# Lightcontrol.net
KiCad netlist of a schematic drawn in EAGLE
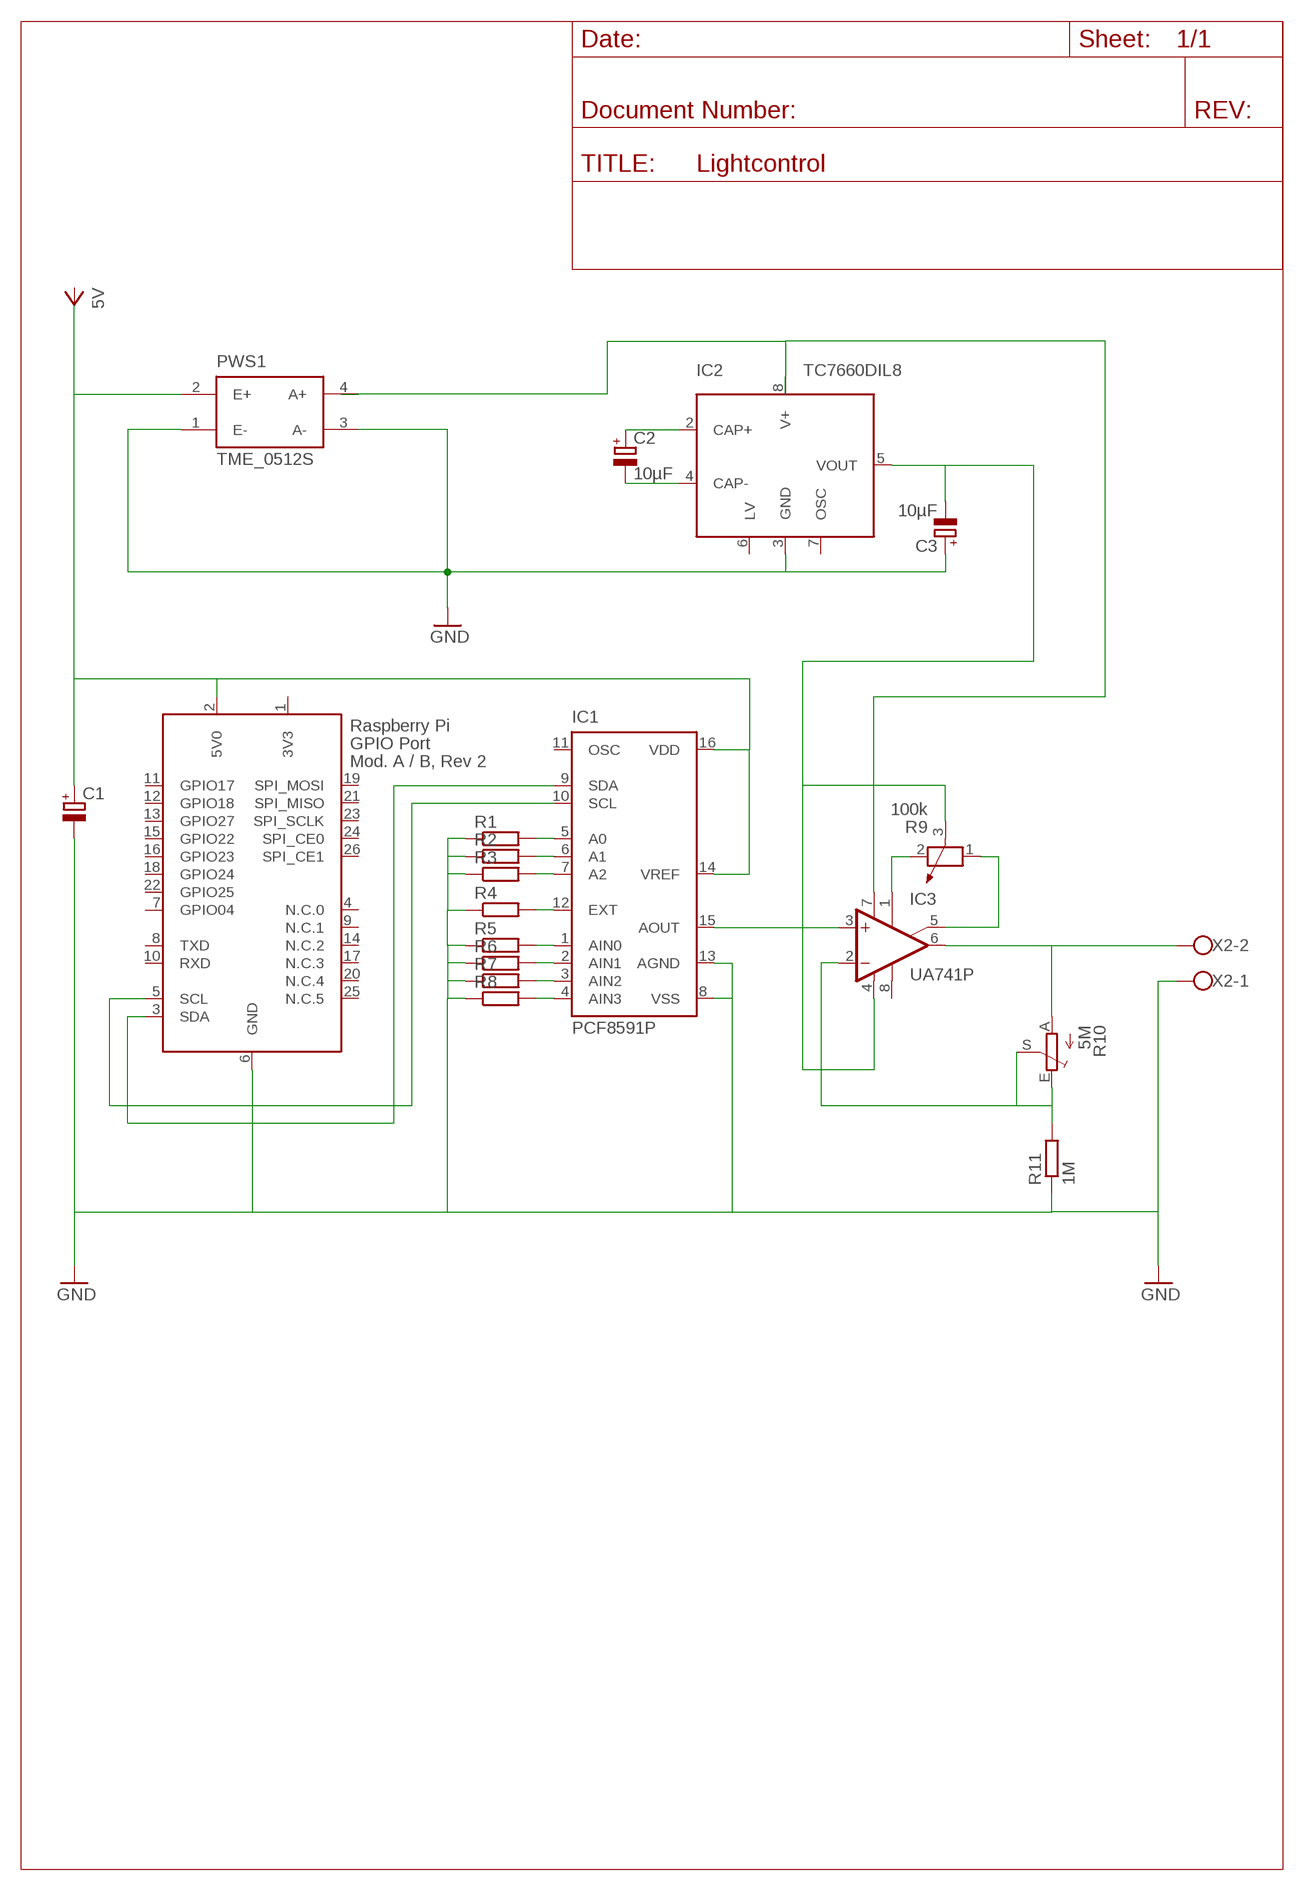
[diagram p0: schematic, sheet 1]

(export (version "E")
  (design (tool "Eeschema 10.0.6"))
  (components
    (comp (ref "C1")
      (value "CPOL-EUE1.8-4")
      (footprint "eagle-import:E1,8-4")
      (libsource (lib "eagle-import") (part "CPOL-EUE1.8-4"))
    )
    (comp (ref "C2")
      (value "10µF")
      (footprint "eagle-import:E1,8-4")
      (libsource (lib "eagle-import") (part "CPOL-EUE1.8-4"))
    )
    (comp (ref "C3")
      (value "10µF")
      (footprint "eagle-import:E1,8-4")
      (libsource (lib "eagle-import") (part "CPOL-EUE1.8-4"))
    )
    (comp (ref "IC1")
      (value "PCF8591P")
      (footprint "eagle-import:DIL16")
      (fields (field (name "MF") "FARNELL"))
      (libsource (lib "eagle-import") (part "PCF8591P"))
    )
    (comp (ref "IC2")
      (value "TC7660DIL8")
      (footprint "eagle-import:DIL8")
      (libsource (lib "eagle-import") (part "TC7660DIL8"))
    )
    (comp (ref "IC3")
      (value "UA741P")
      (footprint "eagle-import:DIL08")
      (libsource (lib "eagle-import") (part "741PUA"))
    )
    (comp (ref "PWS1")
      (value "TME_0512S")
      (footprint "eagle-import:TMEXXXXS")
      (fields (field (name "MPN") "TME 0512S"))
      (libsource (lib "eagle-import") (part "TME_S0512"))
    )
    (comp (ref "R1")
      (value "R-EU_0204/5")
      (footprint "eagle-import:0204_5")
      (libsource (lib "eagle-import") (part "R-EU_0204/5"))
    )
    (comp (ref "R2")
      (value "R-EU_0204/5")
      (footprint "eagle-import:0204_5")
      (libsource (lib "eagle-import") (part "R-EU_0204/5"))
    )
    (comp (ref "R3")
      (value "R-EU_0204/5")
      (footprint "eagle-import:0204_5")
      (libsource (lib "eagle-import") (part "R-EU_0204/5"))
    )
    (comp (ref "R4")
      (value "R-EU_0204/5")
      (footprint "eagle-import:0204_5")
      (libsource (lib "eagle-import") (part "R-EU_0204/5"))
    )
    (comp (ref "R5")
      (value "R-EU_0204/5")
      (footprint "eagle-import:0204_5")
      (libsource (lib "eagle-import") (part "R-EU_0204/5"))
    )
    (comp (ref "R6")
      (value "R-EU_0204/5")
      (footprint "eagle-import:0204_5")
      (libsource (lib "eagle-import") (part "R-EU_0204/5"))
    )
    (comp (ref "R7")
      (value "R-EU_0204/5")
      (footprint "eagle-import:0204_5")
      (libsource (lib "eagle-import") (part "R-EU_0204/5"))
    )
    (comp (ref "R8")
      (value "R-EU_0204/5")
      (footprint "eagle-import:0204_5")
      (libsource (lib "eagle-import") (part "R-EU_0204/5"))
    )
    (comp (ref "R9")
      (value "100k")
      (footprint "eagle-import:PT-10S")
      (libsource (lib "eagle-import") (part "POTENTIOMETER_PT-10S"))
    )
    (comp (ref "R10")
      (value "5M")
      (footprint "eagle-import:ST15")
      (libsource (lib "eagle-import") (part "TRIM_EU-ST15"))
    )
    (comp (ref "R11")
      (value "1M")
      (footprint "eagle-import:0204_5")
      (libsource (lib "eagle-import") (part "R-EU_0204/5"))
    )
    (comp (ref "X1")
      (value "RASPI_GPIO_AB_PIN")
      (footprint "eagle-import:RASPI_GPIO_AB_PIN")
      (libsource (lib "eagle-import") (part "RASPI_GPIO_AB_PIN"))
    )
    (comp (ref "X2")
      (value "W237-102")
      (footprint "eagle-import:W237-102")
      (fields (field (name "MPN") "237-102"))
      (libsource (lib "eagle-import") (part "W237-102"))
    )
  )
  (nets
    (net (code "1") (name "/3V3") (class "Default")
      (node (ref "X1") (pin "1") (pinfunction "3V3_1") (pintype "power_in"))
    )
    (net (code "3") (name "GND") (class "Default")
      (node (ref "C1") (pin "-") (pinfunction "-_-") (pintype "passive"))
      (node (ref "C3") (pin "+") (pinfunction "+_+") (pintype "passive"))
      (node (ref "IC1") (pin "13") (pinfunction "AGND_13") (pintype "power_in"))
      (node (ref "IC1") (pin "8") (pinfunction "VSS_8") (pintype "power_in"))
      (node (ref "IC2") (pin "3") (pinfunction "GND_3") (pintype "bidirectional"))
      (node (ref "PWS1") (pin "1") (pinfunction "E-_1") (pintype "input"))
      (node (ref "PWS1") (pin "3") (pinfunction "A-_3") (pintype "output"))
      (node (ref "R1") (pin "1") (pinfunction "1_1") (pintype "passive"))
      (node (ref "R11") (pin "1") (pinfunction "1_1") (pintype "passive"))
      (node (ref "R2") (pin "1") (pinfunction "1_1") (pintype "passive"))
      (node (ref "R3") (pin "1") (pinfunction "1_1") (pintype "passive"))
      (node (ref "R4") (pin "1") (pinfunction "1_1") (pintype "passive"))
      (node (ref "R5") (pin "1") (pinfunction "1_1") (pintype "passive"))
      (node (ref "R6") (pin "1") (pinfunction "1_1") (pintype "passive"))
      (node (ref "R7") (pin "1") (pinfunction "1_1") (pintype "passive"))
      (node (ref "R8") (pin "1") (pinfunction "1_1") (pintype "passive"))
      (node (ref "X1") (pin "6") (pinfunction "GND_6") (pintype "power_in"))
      (node (ref "X2") (pin "1") (pinfunction "KL_1") (pintype "passive"))
    )
    (net (code "4") (name "Net-(IC1-A0)") (class "Default")
      (node (ref "IC1") (pin "5") (pinfunction "A0_5") (pintype "input"))
      (node (ref "R1") (pin "2") (pinfunction "2_2") (pintype "passive"))
    )
    (net (code "5") (name "Net-(IC1-A1)") (class "Default")
      (node (ref "IC1") (pin "6") (pinfunction "A1_6") (pintype "input"))
      (node (ref "R2") (pin "2") (pinfunction "2_2") (pintype "passive"))
    )
    (net (code "6") (name "Net-(IC1-A2)") (class "Default")
      (node (ref "IC1") (pin "7") (pinfunction "A2_7") (pintype "input"))
      (node (ref "R3") (pin "2") (pinfunction "2_2") (pintype "passive"))
    )
    (net (code "7") (name "Net-(IC1-AIN0)") (class "Default")
      (node (ref "IC1") (pin "1") (pinfunction "AIN0_1") (pintype "input"))
      (node (ref "R5") (pin "2") (pinfunction "2_2") (pintype "passive"))
    )
    (net (code "8") (name "Net-(IC1-AIN1)") (class "Default")
      (node (ref "IC1") (pin "2") (pinfunction "AIN1_2") (pintype "input"))
      (node (ref "R6") (pin "2") (pinfunction "2_2") (pintype "passive"))
    )
    (net (code "9") (name "Net-(IC1-AIN2)") (class "Default")
      (node (ref "IC1") (pin "3") (pinfunction "AIN2_3") (pintype "input"))
      (node (ref "R7") (pin "2") (pinfunction "2_2") (pintype "passive"))
    )
    (net (code "10") (name "Net-(IC1-AIN3)") (class "Default")
      (node (ref "IC1") (pin "4") (pinfunction "AIN3_4") (pintype "input"))
      (node (ref "R8") (pin "2") (pinfunction "2_2") (pintype "passive"))
    )
    (net (code "11") (name "Net-(IC1-AOUT)") (class "Default")
      (node (ref "IC1") (pin "15") (pinfunction "AOUT_15") (pintype "output"))
      (node (ref "IC3") (pin "3") (pinfunction "+IN_3") (pintype "input"))
    )
    (net (code "12") (name "Net-(IC1-EXT)") (class "Default")
      (node (ref "IC1") (pin "12") (pinfunction "EXT_12") (pintype "input"))
      (node (ref "R4") (pin "2") (pinfunction "2_2") (pintype "passive"))
    )
    (net (code "13") (name "Net-(IC1-SCL)") (class "Default")
      (node (ref "IC1") (pin "10") (pinfunction "SCL_10") (pintype "input"))
      (node (ref "X1") (pin "5") (pinfunction "SCL_5") (pintype "bidirectional"))
    )
    (net (code "14") (name "Net-(IC1-SDA)") (class "Default")
      (node (ref "IC1") (pin "9") (pinfunction "SDA_9") (pintype "bidirectional"))
      (node (ref "X1") (pin "3") (pinfunction "SDA_3") (pintype "bidirectional"))
    )
    (net (code "15") (name "Net-(IC1-VDD)") (class "Default")
      (node (ref "C1") (pin "+") (pinfunction "+_+") (pintype "passive"))
      (node (ref "IC1") (pin "14") (pinfunction "VREF_14") (pintype "input"))
      (node (ref "IC1") (pin "16") (pinfunction "VDD_16") (pintype "power_in"))
      (node (ref "PWS1") (pin "2") (pinfunction "E+_2") (pintype "input"))
      (node (ref "X1") (pin "2") (pinfunction "5V0_2") (pintype "power_in"))
    )
    (net (code "16") (name "Net-(IC2-CAP+)") (class "Default")
      (node (ref "C2") (pin "+") (pinfunction "+_+") (pintype "passive"))
      (node (ref "IC2") (pin "2") (pinfunction "CAP+_2") (pintype "bidirectional"))
    )
    (net (code "17") (name "Net-(IC2-CAP-)") (class "Default")
      (node (ref "C2") (pin "-") (pinfunction "-_-") (pintype "passive"))
      (node (ref "IC2") (pin "4") (pinfunction "CAP-_4") (pintype "bidirectional"))
    )
    (net (code "18") (name "Net-(IC2-V+)") (class "Default")
      (node (ref "IC2") (pin "8") (pinfunction "V+_8") (pintype "bidirectional"))
      (node (ref "IC3") (pin "7") (pinfunction "V+_7") (pintype "power_in"))
      (node (ref "PWS1") (pin "4") (pinfunction "A+_4") (pintype "output"))
    )
    (net (code "19") (name "Net-(IC2-VOUT)") (class "Default")
      (node (ref "C3") (pin "-") (pinfunction "-_-") (pintype "passive"))
      (node (ref "IC2") (pin "5") (pinfunction "VOUT_5") (pintype "bidirectional"))
      (node (ref "IC3") (pin "4") (pinfunction "V-_4") (pintype "power_in"))
      (node (ref "R9") (pin "3") (pinfunction "3_3") (pintype "passive"))
    )
    (net (code "20") (name "Net-(IC3--IN)") (class "Default")
      (node (ref "IC3") (pin "2") (pinfunction "-IN_2") (pintype "input"))
      (node (ref "R10") (pin "E") (pinfunction "E_E") (pintype "passive"))
      (node (ref "R10") (pin "S") (pinfunction "S_S") (pintype "passive"))
      (node (ref "R11") (pin "2") (pinfunction "2_2") (pintype "passive"))
    )
    (net (code "21") (name "Net-(IC3-ON1)") (class "Default")
      (node (ref "IC3") (pin "1") (pinfunction "ON1_1") (pintype "passive"))
      (node (ref "R9") (pin "2") (pinfunction "2_2") (pintype "passive"))
    )
    (net (code "22") (name "Net-(IC3-ON2)") (class "Default")
      (node (ref "IC3") (pin "5") (pinfunction "ON2_5") (pintype "passive"))
      (node (ref "R9") (pin "1") (pinfunction "1_1") (pintype "passive"))
    )
    (net (code "23") (name "Net-(IC3-OUT)") (class "Default")
      (node (ref "IC3") (pin "6") (pinfunction "OUT_6") (pintype "output"))
      (node (ref "R10") (pin "A") (pinfunction "A_A") (pintype "passive"))
      (node (ref "X2") (pin "2") (pinfunction "KL_2") (pintype "passive"))
    )
    (net (code "24") (name "unconnected-(IC1-OSC-Pad11)") (class "Default")
      (node (ref "IC1") (pin "11") (pinfunction "OSC_11") (pintype "input"))
    )
    (net (code "25") (name "unconnected-(IC2-LV-Pad6)") (class "Default")
      (node (ref "IC2") (pin "6") (pinfunction "LV_6") (pintype "bidirectional"))
    )
    (net (code "26") (name "unconnected-(IC2-OSC-Pad7)") (class "Default")
      (node (ref "IC2") (pin "7") (pinfunction "OSC_7") (pintype "bidirectional"))
    )
    (net (code "27") (name "unconnected-(IC3-OPT-Pad8)") (class "Default")
      (node (ref "IC3") (pin "8") (pinfunction "OPT_8") (pintype "passive"))
    )
    (net (code "28") (name "unconnected-(X1-GPIO04-Pad7)") (class "Default")
      (node (ref "X1") (pin "7") (pinfunction "GPIO04_7") (pintype "bidirectional"))
    )
    (net (code "29") (name "unconnected-(X1-GPIO17-Pad11)") (class "Default")
      (node (ref "X1") (pin "11") (pinfunction "GPIO17_11") (pintype "bidirectional"))
    )
    (net (code "30") (name "unconnected-(X1-GPIO18-Pad12)") (class "Default")
      (node (ref "X1") (pin "12") (pinfunction "GPIO18_12") (pintype "bidirectional"))
    )
    (net (code "31") (name "unconnected-(X1-GPIO22-Pad15)") (class "Default")
      (node (ref "X1") (pin "15") (pinfunction "GPIO22_15") (pintype "bidirectional"))
    )
    (net (code "32") (name "unconnected-(X1-GPIO23-Pad16)") (class "Default")
      (node (ref "X1") (pin "16") (pinfunction "GPIO23_16") (pintype "bidirectional"))
    )
    (net (code "33") (name "unconnected-(X1-GPIO24-Pad18)") (class "Default")
      (node (ref "X1") (pin "18") (pinfunction "GPIO24_18") (pintype "bidirectional"))
    )
    (net (code "34") (name "unconnected-(X1-GPIO25-Pad22)") (class "Default")
      (node (ref "X1") (pin "22") (pinfunction "GPIO25_22") (pintype "bidirectional"))
    )
    (net (code "35") (name "unconnected-(X1-GPIO27-Pad13)") (class "Default")
      (node (ref "X1") (pin "13") (pinfunction "GPIO27_13") (pintype "bidirectional"))
    )
    (net (code "36") (name "unconnected-(X1-N.C.0-Pad4)") (class "Default")
      (node (ref "X1") (pin "4") (pinfunction "N.C.0_4") (pintype "no_connect"))
    )
    (net (code "37") (name "unconnected-(X1-N.C.1-Pad9)") (class "Default")
      (node (ref "X1") (pin "9") (pinfunction "N.C.1_9") (pintype "no_connect"))
    )
    (net (code "38") (name "unconnected-(X1-N.C.2-Pad14)") (class "Default")
      (node (ref "X1") (pin "14") (pinfunction "N.C.2_14") (pintype "no_connect"))
    )
    (net (code "39") (name "unconnected-(X1-N.C.3-Pad17)") (class "Default")
      (node (ref "X1") (pin "17") (pinfunction "N.C.3_17") (pintype "no_connect"))
    )
    (net (code "40") (name "unconnected-(X1-N.C.4-Pad20)") (class "Default")
      (node (ref "X1") (pin "20") (pinfunction "N.C.4_20") (pintype "no_connect"))
    )
    (net (code "41") (name "unconnected-(X1-N.C.5-Pad25)") (class "Default")
      (node (ref "X1") (pin "25") (pinfunction "N.C.5_25") (pintype "no_connect"))
    )
    (net (code "42") (name "unconnected-(X1-RXD-Pad10)") (class "Default")
      (node (ref "X1") (pin "10") (pinfunction "RXD_10") (pintype "bidirectional"))
    )
    (net (code "43") (name "unconnected-(X1-SPI_CE0-Pad24)") (class "Default")
      (node (ref "X1") (pin "24") (pinfunction "SPI_CE0_24") (pintype "bidirectional"))
    )
    (net (code "44") (name "unconnected-(X1-SPI_CE1-Pad26)") (class "Default")
      (node (ref "X1") (pin "26") (pinfunction "SPI_CE1_26") (pintype "bidirectional"))
    )
    (net (code "45") (name "unconnected-(X1-SPI_MISO-Pad21)") (class "Default")
      (node (ref "X1") (pin "21") (pinfunction "SPI_MISO_21") (pintype "bidirectional"))
    )
    (net (code "46") (name "unconnected-(X1-SPI_MOSI-Pad19)") (class "Default")
      (node (ref "X1") (pin "19") (pinfunction "SPI_MOSI_19") (pintype "bidirectional"))
    )
    (net (code "47") (name "unconnected-(X1-SPI_SCLK-Pad23)") (class "Default")
      (node (ref "X1") (pin "23") (pinfunction "SPI_SCLK_23") (pintype "bidirectional"))
    )
    (net (code "48") (name "unconnected-(X1-TXD-Pad8)") (class "Default")
      (node (ref "X1") (pin "8") (pinfunction "TXD_8") (pintype "bidirectional"))
    )
  )
)
